# SCH_esp32_ubidots_dth11_2022-10-09.net
KiCad netlist of a schematic drawn in EasyEDA
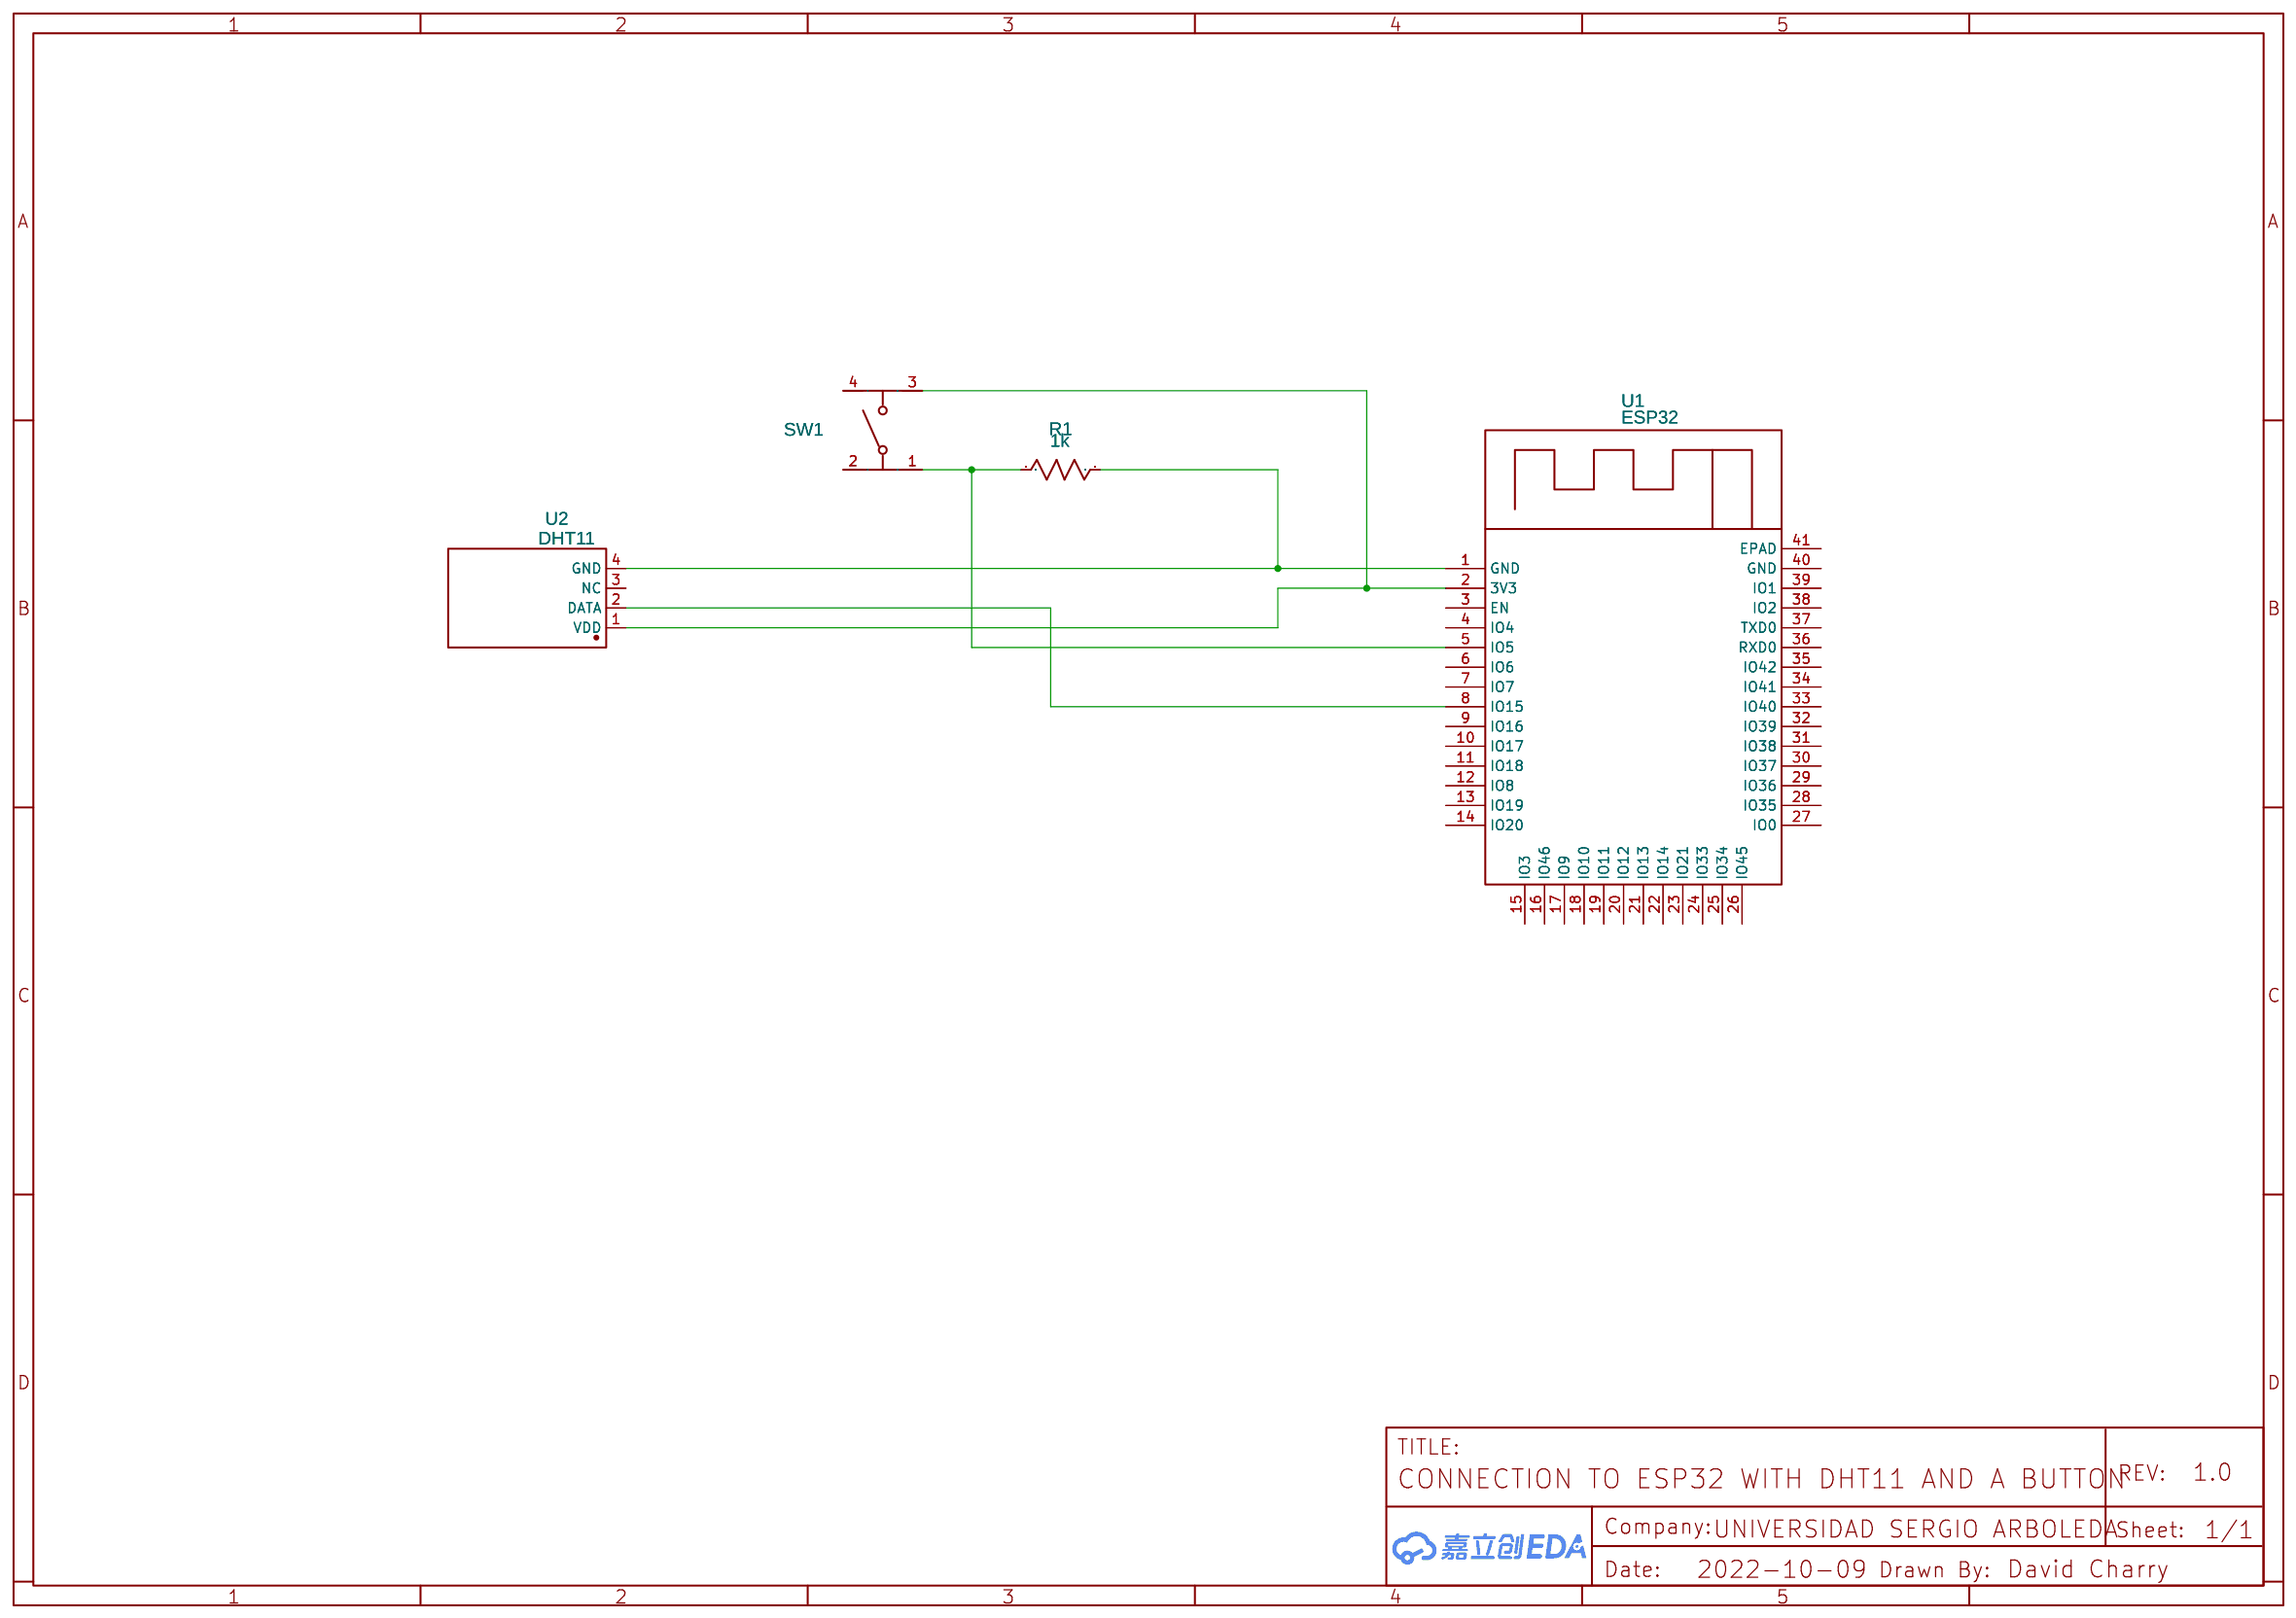
[diagram p0: schematic sheet]

(export (version "E")
  (design (tool "Eeschema 10.0.6"))
  (components
    (comp (ref "R1") (value "1k") (libsource (lib "") (part "R_0603_US")))
    (comp (ref "SW1")
      (value "Button-6x6x6mm")
      (fields
        (field (name "BOM_Manufacturer Part") "Switch,6*6*6Plastic head,260G, 0.25mm,Straight line")
        (field (name "BOM_Supplier Part") "C71836")
      )
      (libsource (lib "") (part "Button-6x6x6mm"))
    )
    (comp (ref "U1")
      (value "ESP32")
      (fields
        (field (name "BOM_Manufacturer Part") "ESP32-S2-SOLO-N4R2")
        (field (name "BOM_Supplier Part") "C3013947")
      )
      (libsource (lib "") (part "ESP32-S2-SOLO-N4R2"))
    )
    (comp (ref "U2")
      (value "DHT11")
      (fields (field (name "BOM_Supplier Part") "C117051"))
      (libsource (lib "") (part "DHT11"))
    )
  )
  (nets
    (net (code "1") (name "Net-(U1-3V3)") (class "Default")
      (node (ref "SW1") (pin "3") (pinfunction "3_3") (pintype "unspecified"))
      (node (ref "U1") (pin "2") (pinfunction "3V3_2") (pintype "passive"))
      (node (ref "U2") (pin "1") (pinfunction "VDD_1") (pintype "unspecified"))
    )
    (net (code "2") (name "Net-(U1-IO5)") (class "Default")
      (node (ref "R1") (pin "2") (pinfunction "2_2") (pintype "unspecified"))
      (node (ref "SW1") (pin "1") (pinfunction "1_1") (pintype "unspecified"))
      (node (ref "U1") (pin "5") (pinfunction "IO5_5") (pintype "bidirectional"))
    )
    (net (code "3") (name "Net-(U1-IO15)") (class "Default")
      (node (ref "U1") (pin "8") (pinfunction "IO15_8") (pintype "bidirectional"))
      (node (ref "U2") (pin "2") (pinfunction "DATA_2") (pintype "unspecified"))
    )
    (net (code "4") (name "Net-(U2-GND)") (class "Default")
      (node (ref "R1") (pin "1") (pinfunction "1_1") (pintype "unspecified"))
      (node (ref "U1") (pin "1") (pinfunction "GND_1") (pintype "passive"))
      (node (ref "U2") (pin "4") (pinfunction "GND_4") (pintype "unspecified"))
    )
    (net (code "5") (name "unconnected-(SW1-Pad2)") (class "Default")
      (node (ref "SW1") (pin "2") (pinfunction "2_2") (pintype "unspecified"))
    )
    (net (code "6") (name "unconnected-(SW1-Pad4)") (class "Default")
      (node (ref "SW1") (pin "4") (pinfunction "4_4") (pintype "unspecified"))
    )
    (net (code "7") (name "unconnected-(U1-EN-Pad3)") (class "Default")
      (node (ref "U1") (pin "3") (pinfunction "EN_3") (pintype "input"))
    )
    (net (code "8") (name "unconnected-(U1-EPAD-Pad41)") (class "Default")
      (node (ref "U1") (pin "41") (pinfunction "EPAD_41") (pintype "passive"))
    )
    (net (code "9") (name "unconnected-(U1-GND-Pad40)") (class "Default")
      (node (ref "U1") (pin "40") (pinfunction "GND_40") (pintype "bidirectional"))
    )
    (net (code "10") (name "unconnected-(U1-IO0-Pad27)") (class "Default")
      (node (ref "U1") (pin "27") (pinfunction "IO0_27") (pintype "bidirectional"))
    )
    (net (code "11") (name "unconnected-(U1-IO1-Pad39)") (class "Default")
      (node (ref "U1") (pin "39") (pinfunction "IO1_39") (pintype "bidirectional"))
    )
    (net (code "12") (name "unconnected-(U1-IO2-Pad38)") (class "Default")
      (node (ref "U1") (pin "38") (pinfunction "IO2_38") (pintype "passive"))
    )
    (net (code "13") (name "unconnected-(U1-IO3-Pad15)") (class "Default")
      (node (ref "U1") (pin "15") (pinfunction "IO3_15") (pintype "passive"))
    )
    (net (code "14") (name "unconnected-(U1-IO4-Pad4)") (class "Default")
      (node (ref "U1") (pin "4") (pinfunction "IO4_4") (pintype "bidirectional"))
    )
    (net (code "15") (name "unconnected-(U1-IO6-Pad6)") (class "Default")
      (node (ref "U1") (pin "6") (pinfunction "IO6_6") (pintype "bidirectional"))
    )
    (net (code "16") (name "unconnected-(U1-IO7-Pad7)") (class "Default")
      (node (ref "U1") (pin "7") (pinfunction "IO7_7") (pintype "bidirectional"))
    )
    (net (code "17") (name "unconnected-(U1-IO8-Pad12)") (class "Default")
      (node (ref "U1") (pin "12") (pinfunction "IO8_12") (pintype "bidirectional"))
    )
    (net (code "18") (name "unconnected-(U1-IO9-Pad17)") (class "Default")
      (node (ref "U1") (pin "17") (pinfunction "IO9_17") (pintype "bidirectional"))
    )
    (net (code "19") (name "unconnected-(U1-IO10-Pad18)") (class "Default")
      (node (ref "U1") (pin "18") (pinfunction "IO10_18") (pintype "bidirectional"))
    )
    (net (code "20") (name "unconnected-(U1-IO11-Pad19)") (class "Default")
      (node (ref "U1") (pin "19") (pinfunction "IO11_19") (pintype "bidirectional"))
    )
    (net (code "21") (name "unconnected-(U1-IO12-Pad20)") (class "Default")
      (node (ref "U1") (pin "20") (pinfunction "IO12_20") (pintype "bidirectional"))
    )
    (net (code "22") (name "unconnected-(U1-IO13-Pad21)") (class "Default")
      (node (ref "U1") (pin "21") (pinfunction "IO13_21") (pintype "bidirectional"))
    )
    (net (code "23") (name "unconnected-(U1-IO14-Pad22)") (class "Default")
      (node (ref "U1") (pin "22") (pinfunction "IO14_22") (pintype "bidirectional"))
    )
    (net (code "24") (name "unconnected-(U1-IO16-Pad9)") (class "Default")
      (node (ref "U1") (pin "9") (pinfunction "IO16_9") (pintype "bidirectional"))
    )
    (net (code "25") (name "unconnected-(U1-IO17-Pad10)") (class "Default")
      (node (ref "U1") (pin "10") (pinfunction "IO17_10") (pintype "bidirectional"))
    )
    (net (code "26") (name "unconnected-(U1-IO18-Pad11)") (class "Default")
      (node (ref "U1") (pin "11") (pinfunction "IO18_11") (pintype "bidirectional"))
    )
    (net (code "27") (name "unconnected-(U1-IO19-Pad13)") (class "Default")
      (node (ref "U1") (pin "13") (pinfunction "IO19_13") (pintype "bidirectional"))
    )
    (net (code "28") (name "unconnected-(U1-IO20-Pad14)") (class "Default")
      (node (ref "U1") (pin "14") (pinfunction "IO20_14") (pintype "bidirectional"))
    )
    (net (code "29") (name "unconnected-(U1-IO21-Pad23)") (class "Default")
      (node (ref "U1") (pin "23") (pinfunction "IO21_23") (pintype "bidirectional"))
    )
    (net (code "30") (name "unconnected-(U1-IO33-Pad24)") (class "Default")
      (node (ref "U1") (pin "24") (pinfunction "IO33_24") (pintype "bidirectional"))
    )
    (net (code "31") (name "unconnected-(U1-IO34-Pad25)") (class "Default")
      (node (ref "U1") (pin "25") (pinfunction "IO34_25") (pintype "bidirectional"))
    )
    (net (code "32") (name "unconnected-(U1-IO35-Pad28)") (class "Default")
      (node (ref "U1") (pin "28") (pinfunction "IO35_28") (pintype "bidirectional"))
    )
    (net (code "33") (name "unconnected-(U1-IO36-Pad29)") (class "Default")
      (node (ref "U1") (pin "29") (pinfunction "IO36_29") (pintype "bidirectional"))
    )
    (net (code "34") (name "unconnected-(U1-IO37-Pad30)") (class "Default")
      (node (ref "U1") (pin "30") (pinfunction "IO37_30") (pintype "bidirectional"))
    )
    (net (code "35") (name "unconnected-(U1-IO38-Pad31)") (class "Default")
      (node (ref "U1") (pin "31") (pinfunction "IO38_31") (pintype "bidirectional"))
    )
    (net (code "36") (name "unconnected-(U1-IO39-Pad32)") (class "Default")
      (node (ref "U1") (pin "32") (pinfunction "IO39_32") (pintype "bidirectional"))
    )
    (net (code "37") (name "unconnected-(U1-IO40-Pad33)") (class "Default")
      (node (ref "U1") (pin "33") (pinfunction "IO40_33") (pintype "bidirectional"))
    )
    (net (code "38") (name "unconnected-(U1-IO41-Pad34)") (class "Default")
      (node (ref "U1") (pin "34") (pinfunction "IO41_34") (pintype "input"))
    )
    (net (code "39") (name "unconnected-(U1-IO42-Pad35)") (class "Default")
      (node (ref "U1") (pin "35") (pinfunction "IO42_35") (pintype "output"))
    )
    (net (code "40") (name "unconnected-(U1-IO45-Pad26)") (class "Default")
      (node (ref "U1") (pin "26") (pinfunction "IO45_26") (pintype "bidirectional"))
    )
    (net (code "41") (name "unconnected-(U1-IO46-Pad16)") (class "Default")
      (node (ref "U1") (pin "16") (pinfunction "IO46_16") (pintype "bidirectional"))
    )
    (net (code "42") (name "unconnected-(U1-RXD0-Pad36)") (class "Default")
      (node (ref "U1") (pin "36") (pinfunction "RXD0_36") (pintype "bidirectional"))
    )
    (net (code "43") (name "unconnected-(U1-TXD0-Pad37)") (class "Default")
      (node (ref "U1") (pin "37") (pinfunction "TXD0_37") (pintype "bidirectional"))
    )
    (net (code "44") (name "unconnected-(U2-NC-Pad3)") (class "Default")
      (node (ref "U2") (pin "3") (pinfunction "NC_3") (pintype "unspecified"))
    )
  )
)
